# I2Cbasic.net
KiCad netlist of a schematic drawn in EAGLE
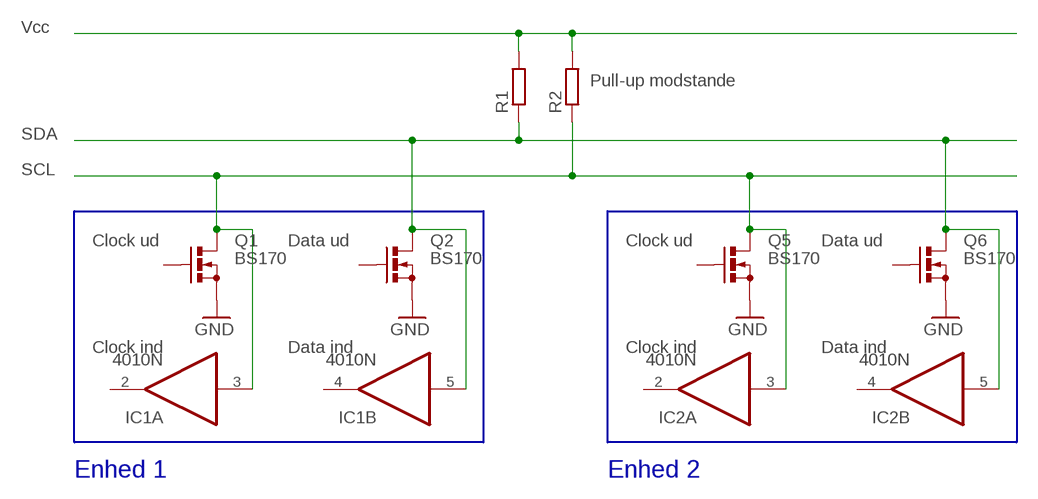
[diagram p0: schematic, sheet 1]

(export (version "E")
  (design (tool "Eeschema 10.0.6"))
  (components
    (comp (ref "IC1")
      (value "4010N")
      (footprint "eagle-import:DIL16")
      (libsource (lib "eagle-import") (part "4010N"))
    )
    (comp (ref "IC2")
      (value "4010N")
      (footprint "eagle-import:DIL16")
      (libsource (lib "eagle-import") (part "4010N"))
    )
    (comp (ref "Q1")
      (value "BS170")
      (footprint "eagle-import:SOT54E")
      (libsource (lib "eagle-import") (part "BS170"))
    )
    (comp (ref "Q2")
      (value "BS170")
      (footprint "eagle-import:SOT54E")
      (libsource (lib "eagle-import") (part "BS170"))
    )
    (comp (ref "Q5")
      (value "BS170")
      (footprint "eagle-import:SOT54E")
      (libsource (lib "eagle-import") (part "BS170"))
    )
    (comp (ref "Q6")
      (value "BS170")
      (footprint "eagle-import:SOT54E")
      (libsource (lib "eagle-import") (part "BS170"))
    )
    (comp (ref "R1")
      (value "R-EU_0207/10")
      (footprint "eagle-import:0207_10")
      (libsource (lib "eagle-import") (part "R-EU_0207/10"))
    )
    (comp (ref "R2")
      (value "R-EU_0207/10")
      (footprint "eagle-import:0207_10")
      (libsource (lib "eagle-import") (part "R-EU_0207/10"))
    )
  )
  (nets
    (net (code "1") (name "GND") (class "Default")
      (node (ref "Q1") (pin "S") (pinfunction "S_S") (pintype "passive"))
      (node (ref "Q2") (pin "S") (pinfunction "S_S") (pintype "passive"))
      (node (ref "Q5") (pin "S") (pinfunction "S_S") (pintype "passive"))
      (node (ref "Q6") (pin "S") (pinfunction "S_S") (pintype "passive"))
    )
    (net (code "2") (name "Net-(IC1A-I)") (class "Default")
      (node (ref "IC1") (pin "3") (pinfunction "I_3") (pintype "input"))
      (node (ref "IC2") (pin "3") (pinfunction "I_3") (pintype "input"))
      (node (ref "Q1") (pin "D") (pinfunction "D_D") (pintype "passive"))
      (node (ref "Q5") (pin "D") (pinfunction "D_D") (pintype "passive"))
      (node (ref "R2") (pin "1") (pinfunction "1_1") (pintype "passive"))
    )
    (net (code "3") (name "Net-(IC1B-I)") (class "Default")
      (node (ref "IC1") (pin "5") (pinfunction "I_5") (pintype "input"))
      (node (ref "IC2") (pin "5") (pinfunction "I_5") (pintype "input"))
      (node (ref "Q2") (pin "D") (pinfunction "D_D") (pintype "passive"))
      (node (ref "Q6") (pin "D") (pinfunction "D_D") (pintype "passive"))
      (node (ref "R1") (pin "1") (pinfunction "1_1") (pintype "passive"))
    )
    (net (code "4") (name "Net-(R1-Pad2)") (class "Default")
      (node (ref "R1") (pin "2") (pinfunction "2_2") (pintype "passive"))
      (node (ref "R2") (pin "2") (pinfunction "2_2") (pintype "passive"))
    )
    (net (code "5") (name "unconnected-(IC1A-O-Pad2)") (class "Default")
      (node (ref "IC1") (pin "2") (pinfunction "O_2") (pintype "output"))
    )
    (net (code "6") (name "unconnected-(IC1B-O-Pad4)") (class "Default")
      (node (ref "IC1") (pin "4") (pinfunction "O_4") (pintype "output"))
    )
    (net (code "7") (name "unconnected-(IC2A-O-Pad2)") (class "Default")
      (node (ref "IC2") (pin "2") (pinfunction "O_2") (pintype "output"))
    )
    (net (code "8") (name "unconnected-(IC2B-O-Pad4)") (class "Default")
      (node (ref "IC2") (pin "4") (pinfunction "O_4") (pintype "output"))
    )
    (net (code "9") (name "unconnected-(Q1-PadG)") (class "Default")
      (node (ref "Q1") (pin "G") (pinfunction "G_G") (pintype "passive"))
    )
    (net (code "10") (name "unconnected-(Q2-PadG)") (class "Default")
      (node (ref "Q2") (pin "G") (pinfunction "G_G") (pintype "passive"))
    )
    (net (code "11") (name "unconnected-(Q5-PadG)") (class "Default")
      (node (ref "Q5") (pin "G") (pinfunction "G_G") (pintype "passive"))
    )
    (net (code "12") (name "unconnected-(Q6-PadG)") (class "Default")
      (node (ref "Q6") (pin "G") (pinfunction "G_G") (pintype "passive"))
    )
  )
)
